# IoT_Bee_hive_scale.net
KiCad netlist of a schematic drawn in EAGLE
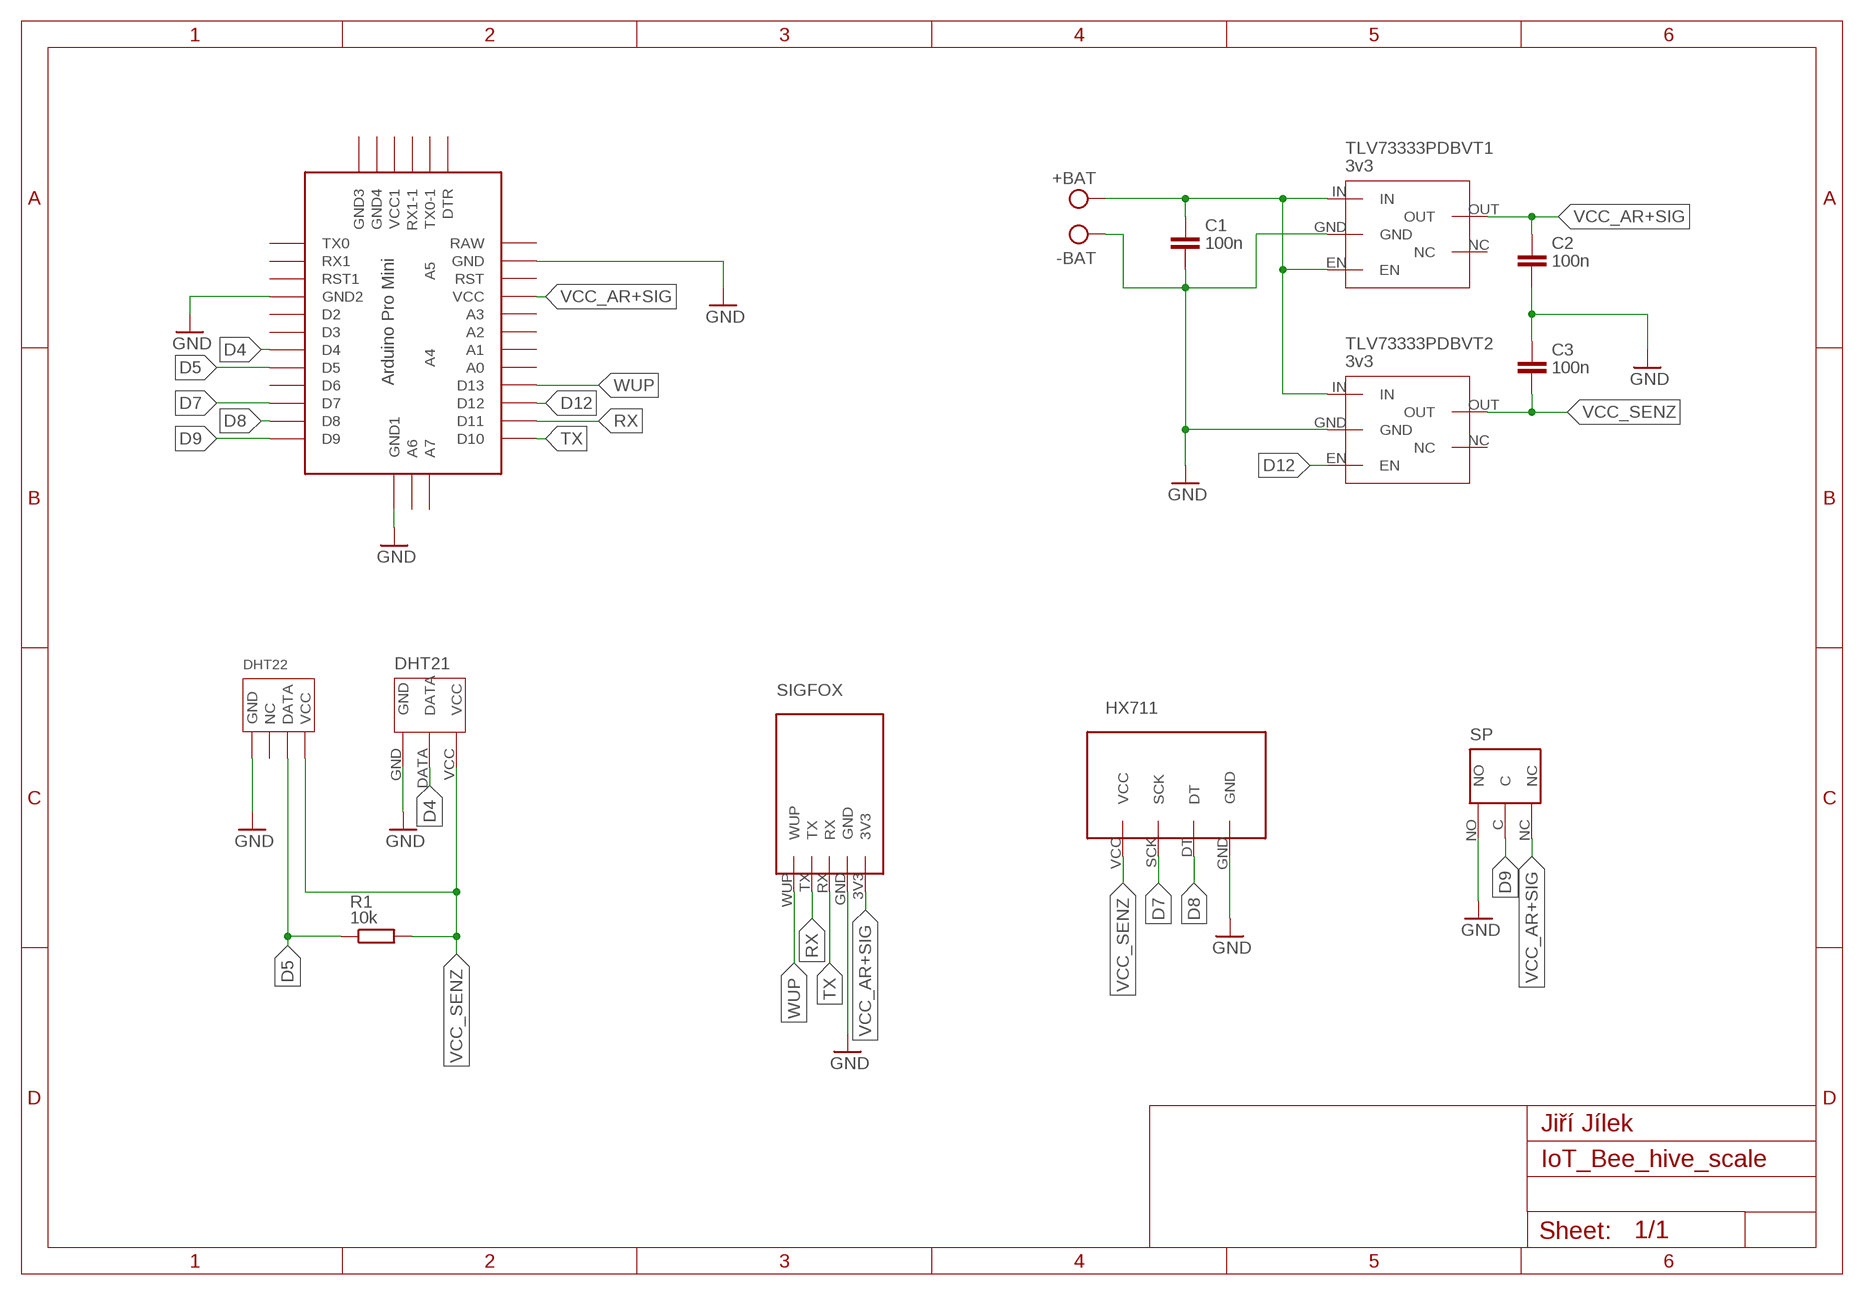
[diagram p0: schematic, sheet 1]

(export (version "E")
  (design (tool "Eeschema 10.0.6"))
  (components
    (comp (ref "+BAT")
      (value "3.7V")
      (footprint "eagle-import:AK300_2")
      (libsource (lib "eagle-import") (part "AK300/2"))
    )
    (comp (ref "C1")
      (value "100n")
      (footprint "eagle-import:C1206")
      (libsource (lib "eagle-import") (part "C-EUC1206"))
    )
    (comp (ref "C2")
      (value "100n")
      (footprint "eagle-import:C1206")
      (libsource (lib "eagle-import") (part "C-EUC1206"))
    )
    (comp (ref "C3")
      (value "100n")
      (footprint "eagle-import:C1206")
      (libsource (lib "eagle-import") (part "C-EUC1206"))
    )
    (comp (ref "DHT21")
      (value "0")
      (footprint "eagle-import:DHT21")
      (libsource (lib "eagle-import") (part "DHT21"))
    )
    (comp (ref "DHT22")
      (value "DHT22")
      (footprint "eagle-import:DHT22")
      (fields (field (name "MF") "Seeed Technology") (field (name "MP") "AM2302"))
      (libsource (lib "eagle-import") (part "DHT22"))
    )
    (comp (ref "HX711")
      (value "0")
      (footprint "eagle-import:HX711")
      (libsource (lib "eagle-import") (part "HX711"))
    )
    (comp (ref "R1")
      (value "10k")
      (footprint "eagle-import:R0805")
      (libsource (lib "eagle-import") (part "R-EU_R0805"))
    )
    (comp (ref "SIGFOX")
      (value "0")
      (footprint "eagle-import:SIGFOX_NODE")
      (libsource (lib "eagle-import") (part "SIGFOX_NODE"))
    )
    (comp (ref "SP")
      (value "0")
      (footprint "eagle-import:MIKROSP")
      (libsource (lib "eagle-import") (part "MIKROSP"))
    )
    (comp (ref "TLV73333PDBVT1")
      (value "3v3")
      (footprint "eagle-import:SOT95P280X145-5N")
      (libsource (lib "eagle-import") (part "TLV73333PDBVT"))
    )
    (comp (ref "TLV73333PDBVT2")
      (value "3v3")
      (footprint "eagle-import:SOT95P280X145-5N")
      (libsource (lib "eagle-import") (part "TLV73333PDBVT"))
    )
    (comp (ref "U$1")
      (value "ABK-PRO-MINI")
      (footprint "eagle-import:ABK-PRO-MINI")
      (libsource (lib "eagle-import") (part "ABK-PRO-MINI"))
    )
  )
  (nets
    (net (code "1") (name "D4") (class "Default")
      (node (ref "DHT21") (pin "DATA") (pinfunction "DATA_DATA") (pintype "bidirectional"))
      (node (ref "U$1") (pin "D4") (pinfunction "D4_D4") (pintype "bidirectional"))
    )
    (net (code "2") (name "D5") (class "Default")
      (node (ref "DHT22") (pin "DATA") (pinfunction "DATA_DATA") (pintype "bidirectional"))
      (node (ref "R1") (pin "1") (pinfunction "1_1") (pintype "passive"))
      (node (ref "U$1") (pin "D5") (pinfunction "D5_D5") (pintype "bidirectional"))
    )
    (net (code "3") (name "D7") (class "Default")
      (node (ref "HX711") (pin "SCK") (pinfunction "SCK_SCK") (pintype "bidirectional"))
      (node (ref "U$1") (pin "D7") (pinfunction "D7_D7") (pintype "bidirectional"))
    )
    (net (code "4") (name "D8") (class "Default")
      (node (ref "HX711") (pin "DT") (pinfunction "DT_DT") (pintype "bidirectional"))
      (node (ref "U$1") (pin "D8") (pinfunction "D8_D8") (pintype "bidirectional"))
    )
    (net (code "5") (name "D9") (class "Default")
      (node (ref "SP") (pin "C") (pinfunction "C_C") (pintype "bidirectional"))
      (node (ref "U$1") (pin "D9") (pinfunction "D9_D9") (pintype "bidirectional"))
    )
    (net (code "6") (name "D12") (class "Default")
      (node (ref "TLV73333PDBVT2") (pin "EN") (pinfunction "EN_EN") (pintype "bidirectional"))
      (node (ref "U$1") (pin "D12") (pinfunction "D12_D12") (pintype "bidirectional"))
    )
    (net (code "7") (name "GND") (class "Default")
      (node (ref "+BAT") (pin "2") (pinfunction "KL_2") (pintype "passive"))
      (node (ref "C1") (pin "2") (pinfunction "2_2") (pintype "passive"))
      (node (ref "C2") (pin "2") (pinfunction "2_2") (pintype "passive"))
      (node (ref "C3") (pin "1") (pinfunction "1_1") (pintype "passive"))
      (node (ref "DHT21") (pin "GND") (pinfunction "GND_GND") (pintype "bidirectional"))
      (node (ref "DHT22") (pin "GND") (pinfunction "GND_GND") (pintype "power_in"))
      (node (ref "HX711") (pin "GND") (pinfunction "GND_GND") (pintype "bidirectional"))
      (node (ref "SIGFOX") (pin "GND") (pinfunction "GND_GND") (pintype "bidirectional"))
      (node (ref "SP") (pin "NO") (pinfunction "NO_NO") (pintype "bidirectional"))
      (node (ref "TLV73333PDBVT1") (pin "GND") (pinfunction "GND_GND") (pintype "bidirectional"))
      (node (ref "TLV73333PDBVT2") (pin "GND") (pinfunction "GND_GND") (pintype "bidirectional"))
      (node (ref "U$1") (pin "GND") (pinfunction "GND_GND") (pintype "bidirectional"))
      (node (ref "U$1") (pin "GND1") (pinfunction "GND2_GND1") (pintype "bidirectional"))
      (node (ref "U$1") (pin "GND4") (pinfunction "GND1_GND4") (pintype "bidirectional"))
    )
    (net (code "8") (name "Net-(+BATA-KL)") (class "Default")
      (node (ref "+BAT") (pin "1") (pinfunction "KL_1") (pintype "passive"))
      (node (ref "C1") (pin "1") (pinfunction "1_1") (pintype "passive"))
      (node (ref "TLV73333PDBVT1") (pin "EN") (pinfunction "EN_EN") (pintype "bidirectional"))
      (node (ref "TLV73333PDBVT1") (pin "IN") (pinfunction "IN_IN") (pintype "bidirectional"))
      (node (ref "TLV73333PDBVT2") (pin "IN") (pinfunction "IN_IN") (pintype "bidirectional"))
    )
    (net (code "9") (name "RX") (class "Default")
      (node (ref "SIGFOX") (pin "TX") (pinfunction "TX_TX") (pintype "bidirectional"))
      (node (ref "U$1") (pin "D11") (pinfunction "D11_D11") (pintype "bidirectional"))
    )
    (net (code "10") (name "TX") (class "Default")
      (node (ref "SIGFOX") (pin "RX") (pinfunction "RX_RX") (pintype "bidirectional"))
      (node (ref "U$1") (pin "D10") (pinfunction "D10_D10") (pintype "bidirectional"))
    )
    (net (code "11") (name "VCC_AR+SIG") (class "Default")
      (node (ref "C2") (pin "1") (pinfunction "1_1") (pintype "passive"))
      (node (ref "SIGFOX") (pin "3V3") (pinfunction "3V3_3V3") (pintype "bidirectional"))
      (node (ref "SP") (pin "NC") (pinfunction "NC_NC") (pintype "bidirectional"))
      (node (ref "TLV73333PDBVT1") (pin "OUT") (pinfunction "OUT_OUT") (pintype "bidirectional"))
      (node (ref "U$1") (pin "VCC") (pinfunction "VCC_VCC") (pintype "bidirectional"))
    )
    (net (code "12") (name "VCC_SENZ") (class "Default")
      (node (ref "C3") (pin "2") (pinfunction "2_2") (pintype "passive"))
      (node (ref "DHT21") (pin "VCC") (pinfunction "VCC_VCC") (pintype "bidirectional"))
      (node (ref "DHT22") (pin "VCC") (pinfunction "VCC_VCC") (pintype "power_in"))
      (node (ref "HX711") (pin "VCC") (pinfunction "VCC_VCC") (pintype "bidirectional"))
      (node (ref "R1") (pin "2") (pinfunction "2_2") (pintype "passive"))
      (node (ref "TLV73333PDBVT2") (pin "OUT") (pinfunction "OUT_OUT") (pintype "bidirectional"))
    )
    (net (code "13") (name "WUP") (class "Default")
      (node (ref "SIGFOX") (pin "WUP") (pinfunction "WUP_WUP") (pintype "bidirectional"))
      (node (ref "U$1") (pin "D13") (pinfunction "D13_D13") (pintype "bidirectional"))
    )
    (net (code "14") (name "unconnected-(DHT22-PadNC)") (class "Default")
      (node (ref "DHT22") (pin "NC") (pinfunction "NC_NC") (pintype "no_connect"))
    )
    (net (code "15") (name "unconnected-(TLV73333PDBVT1-PadNC)") (class "Default")
      (node (ref "TLV73333PDBVT1") (pin "NC") (pinfunction "NC_NC") (pintype "bidirectional"))
    )
    (net (code "16") (name "unconnected-(TLV73333PDBVT2-PadNC)") (class "Default")
      (node (ref "TLV73333PDBVT2") (pin "NC") (pinfunction "NC_NC") (pintype "bidirectional"))
    )
    (net (code "17") (name "unconnected-(U$1-GND3-PadGND2)") (class "Default")
      (node (ref "U$1") (pin "GND2") (pinfunction "GND3_GND2") (pintype "bidirectional"))
    )
    (net (code "18") (name "unconnected-(U$1-GND4-PadGND3)") (class "Default")
      (node (ref "U$1") (pin "GND3") (pinfunction "GND4_GND3") (pintype "bidirectional"))
    )
    (net (code "19") (name "unconnected-(U$1-PadA0)") (class "Default")
      (node (ref "U$1") (pin "A0") (pinfunction "A0_A0") (pintype "bidirectional"))
    )
    (net (code "20") (name "unconnected-(U$1-PadA1)") (class "Default")
      (node (ref "U$1") (pin "A1") (pinfunction "A1_A1") (pintype "bidirectional"))
    )
    (net (code "21") (name "unconnected-(U$1-PadA2)") (class "Default")
      (node (ref "U$1") (pin "A2") (pinfunction "A2_A2") (pintype "bidirectional"))
    )
    (net (code "22") (name "unconnected-(U$1-PadA3)") (class "Default")
      (node (ref "U$1") (pin "A3") (pinfunction "A3_A3") (pintype "bidirectional"))
    )
    (net (code "23") (name "unconnected-(U$1-PadA4)") (class "Default")
      (node (ref "U$1") (pin "A4") (pinfunction "A4_A4") (pintype "bidirectional"))
    )
    (net (code "24") (name "unconnected-(U$1-PadA5)") (class "Default")
      (node (ref "U$1") (pin "A5") (pinfunction "A5_A5") (pintype "bidirectional"))
    )
    (net (code "25") (name "unconnected-(U$1-PadA6)") (class "Default")
      (node (ref "U$1") (pin "A6") (pinfunction "A6_A6") (pintype "bidirectional"))
    )
    (net (code "26") (name "unconnected-(U$1-PadA7)") (class "Default")
      (node (ref "U$1") (pin "A7") (pinfunction "A7_A7") (pintype "bidirectional"))
    )
    (net (code "27") (name "unconnected-(U$1-PadD2)") (class "Default")
      (node (ref "U$1") (pin "D2") (pinfunction "D2_D2") (pintype "bidirectional"))
    )
    (net (code "28") (name "unconnected-(U$1-PadD3)") (class "Default")
      (node (ref "U$1") (pin "D3") (pinfunction "D3_D3") (pintype "bidirectional"))
    )
    (net (code "29") (name "unconnected-(U$1-PadD6)") (class "Default")
      (node (ref "U$1") (pin "D6") (pinfunction "D6_D6") (pintype "bidirectional"))
    )
    (net (code "30") (name "unconnected-(U$1-PadDTR)") (class "Default")
      (node (ref "U$1") (pin "DTR") (pinfunction "DTR_DTR") (pintype "bidirectional"))
    )
    (net (code "31") (name "unconnected-(U$1-PadRAW)") (class "Default")
      (node (ref "U$1") (pin "RAW") (pinfunction "RAW_RAW") (pintype "bidirectional"))
    )
    (net (code "32") (name "unconnected-(U$1-PadRST)") (class "Default")
      (node (ref "U$1") (pin "RST") (pinfunction "RST_RST") (pintype "bidirectional"))
    )
    (net (code "33") (name "unconnected-(U$1-PadRST1)") (class "Default")
      (node (ref "U$1") (pin "RST1") (pinfunction "RST1_RST1") (pintype "bidirectional"))
    )
    (net (code "34") (name "unconnected-(U$1-PadRX1)") (class "Default")
      (node (ref "U$1") (pin "RX1") (pinfunction "RX1_RX1") (pintype "bidirectional"))
    )
    (net (code "35") (name "unconnected-(U$1-PadRX1-1)") (class "Default")
      (node (ref "U$1") (pin "RX1-1") (pinfunction "RX1-1_RX1-1") (pintype "bidirectional"))
    )
    (net (code "36") (name "unconnected-(U$1-PadTX0)") (class "Default")
      (node (ref "U$1") (pin "TX0") (pinfunction "TX0_TX0") (pintype "bidirectional"))
    )
    (net (code "37") (name "unconnected-(U$1-PadTX0-1)") (class "Default")
      (node (ref "U$1") (pin "TX0-1") (pinfunction "TX0-1_TX0-1") (pintype "bidirectional"))
    )
    (net (code "38") (name "unconnected-(U$1-PadVCC1)") (class "Default")
      (node (ref "U$1") (pin "VCC1") (pinfunction "VCC1_VCC1") (pintype "bidirectional"))
    )
  )
)
